# TriangleLEDBoard.net
KiCad netlist of a schematic drawn in EAGLE
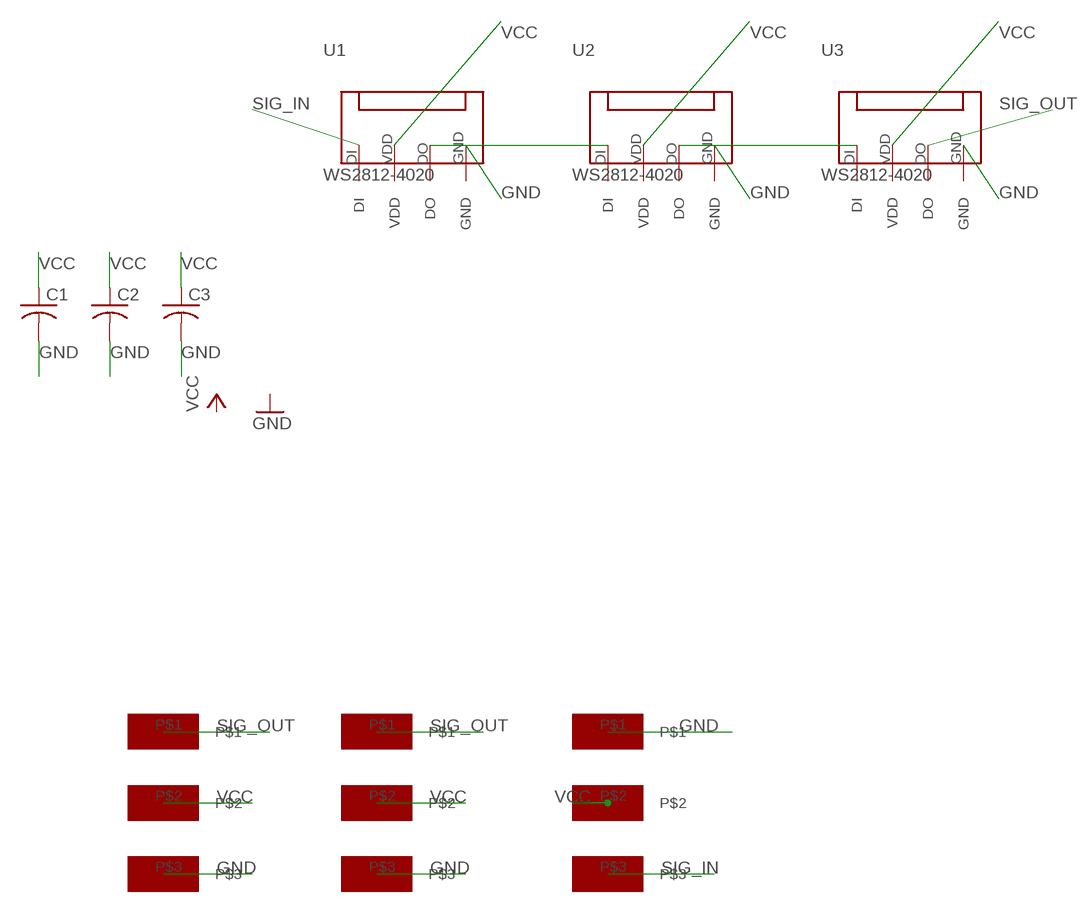
[diagram p0: schematic, sheet 1]

(export (version "E")
  (design (tool "Eeschema 10.0.6"))
  (components
    (comp (ref "C1")
      (value "C-USC0603")
      (footprint "eagle-import:C0603")
      (libsource (lib "eagle-import") (part "C-USC0603"))
    )
    (comp (ref "C2")
      (value "C-USC0603")
      (footprint "eagle-import:C0603")
      (libsource (lib "eagle-import") (part "C-USC0603"))
    )
    (comp (ref "C3")
      (value "C-USC0603")
      (footprint "eagle-import:C0603")
      (libsource (lib "eagle-import") (part "C-USC0603"))
    )
    (comp (ref "U$1")
      (value "3_CONTACT_PADS_5_MM_SPACING_WITH_HOLES")
      (footprint "eagle-import:RECTANGULAR_PADS_5_MM_SPACING_WITH_HOLES")
      (libsource (lib "eagle-import") (part "3_CONTACT_PADS_5_MM_SPACING_WITH_HOLES"))
    )
    (comp (ref "U$2")
      (value "3_CONTACT_PADS_5_MM_SPACING_WITH_HOLES")
      (footprint "eagle-import:RECTANGULAR_PADS_5_MM_SPACING_WITH_HOLES")
      (libsource (lib "eagle-import") (part "3_CONTACT_PADS_5_MM_SPACING_WITH_HOLES"))
    )
    (comp (ref "U$3")
      (value "3_CONTACT_PADS_5_MM_SPACING_WITH_HOLES")
      (footprint "eagle-import:RECTANGULAR_PADS_5_MM_SPACING_WITH_HOLES")
      (libsource (lib "eagle-import") (part "3_CONTACT_PADS_5_MM_SPACING_WITH_HOLES"))
    )
    (comp (ref "U1")
      (value "WS2812-4020")
      (footprint "eagle-import:WS2812B_4020")
      (libsource (lib "eagle-import") (part "WS2812-4020"))
    )
    (comp (ref "U2")
      (value "WS2812-4020")
      (footprint "eagle-import:WS2812B_4020")
      (libsource (lib "eagle-import") (part "WS2812-4020"))
    )
    (comp (ref "U3")
      (value "WS2812-4020")
      (footprint "eagle-import:WS2812B_4020")
      (libsource (lib "eagle-import") (part "WS2812-4020"))
    )
  )
  (nets
    (net (code "1") (name "/SIG_IN") (class "Default")
      (node (ref "U$1") (pin "P$3") (pinfunction "P$3_P$3") (pintype "bidirectional"))
      (node (ref "U1") (pin "DI") (pinfunction "DI_DI") (pintype "bidirectional"))
    )
    (net (code "2") (name "/SIG_OUT") (class "Default")
      (node (ref "U$2") (pin "P$1") (pinfunction "P$1_P$1") (pintype "bidirectional"))
      (node (ref "U$3") (pin "P$1") (pinfunction "P$1_P$1") (pintype "bidirectional"))
      (node (ref "U3") (pin "DO") (pinfunction "DO_DO") (pintype "bidirectional"))
    )
    (net (code "3") (name "GND") (class "Default")
      (node (ref "C1") (pin "2") (pinfunction "2_2") (pintype "passive"))
      (node (ref "C2") (pin "2") (pinfunction "2_2") (pintype "passive"))
      (node (ref "C3") (pin "2") (pinfunction "2_2") (pintype "passive"))
      (node (ref "U$1") (pin "P$1") (pinfunction "P$1_P$1") (pintype "bidirectional"))
      (node (ref "U$2") (pin "P$3") (pinfunction "P$3_P$3") (pintype "bidirectional"))
      (node (ref "U$3") (pin "P$3") (pinfunction "P$3_P$3") (pintype "bidirectional"))
      (node (ref "U1") (pin "GND") (pinfunction "GND_GND") (pintype "bidirectional"))
      (node (ref "U2") (pin "GND") (pinfunction "GND_GND") (pintype "bidirectional"))
      (node (ref "U3") (pin "GND") (pinfunction "GND_GND") (pintype "bidirectional"))
    )
    (net (code "4") (name "Net-(U1-PadDO)") (class "Default")
      (node (ref "U1") (pin "DO") (pinfunction "DO_DO") (pintype "bidirectional"))
      (node (ref "U2") (pin "DI") (pinfunction "DI_DI") (pintype "bidirectional"))
    )
    (net (code "5") (name "Net-(U2-PadDO)") (class "Default")
      (node (ref "U2") (pin "DO") (pinfunction "DO_DO") (pintype "bidirectional"))
      (node (ref "U3") (pin "DI") (pinfunction "DI_DI") (pintype "bidirectional"))
    )
    (net (code "6") (name "VCC") (class "Default")
      (node (ref "C1") (pin "1") (pinfunction "1_1") (pintype "passive"))
      (node (ref "C2") (pin "1") (pinfunction "1_1") (pintype "passive"))
      (node (ref "C3") (pin "1") (pinfunction "1_1") (pintype "passive"))
      (node (ref "U$1") (pin "P$2") (pinfunction "P$2_P$2") (pintype "bidirectional"))
      (node (ref "U$2") (pin "P$2") (pinfunction "P$2_P$2") (pintype "bidirectional"))
      (node (ref "U$3") (pin "P$2") (pinfunction "P$2_P$2") (pintype "bidirectional"))
      (node (ref "U1") (pin "VDD") (pinfunction "VDD_VDD") (pintype "bidirectional"))
      (node (ref "U2") (pin "VDD") (pinfunction "VDD_VDD") (pintype "bidirectional"))
      (node (ref "U3") (pin "VDD") (pinfunction "VDD_VDD") (pintype "bidirectional"))
    )
  )
)
